# RELAY12.net
KiCad netlist of a schematic drawn in Altium Designer
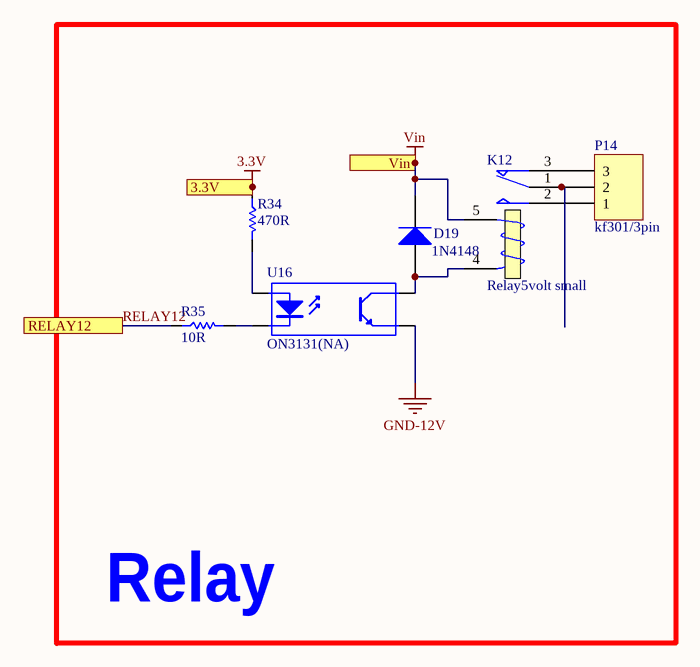
[diagram p0: RELAY12.SchDoc]

(export (version "E")
  (design (tool "Eeschema 10.0.6"))
  (components
    (comp (ref "D19")
      (value "1N4148")
      (footprint "sod123")
      (description "1 Amp General Purpose Rectifier")
      (fields (field (name "PUBLISHER") "Altium Limited"))
      (libsource (lib "Miscellaneous Devices") (part "Diode 1N4007"))
    )
    (comp (ref "K12")
      (value "Relay5volt small")
      (footprint "relay5_childern")
      (description "SPDT Relay")
      (fields (field (name "PUBLISHER") "Altium Limited"))
      (libsource (lib "FLIB") (part "Relay"))
    )
    (comp (ref "P14")
      (value "kf301/3pin")
      (footprint "Blue Connector 1*3 -kf301")
      (fields (field (name "PUBLISHER") "Altium Limited"))
      (libsource (lib "Miscellaneous Connectors") (part "Header 3"))
    )
    (comp (ref "R34")
      (value "470R")
      (footprint "0805/resistor")
      (description "Resistor")
      (fields (field (name "TOLERANCE") "5%") (field (name "POWER") "1/8 W"))
      (libsource (lib "skille") (part "Resistor"))
    )
    (comp (ref "R35")
      (value "10R")
      (footprint "0805/resistor")
      (description "Resistor")
      (fields (field (name "TOLERANCE") "5%") (field (name "POWER") "1/8 W"))
      (libsource (lib "skille") (part "Resistor"))
    )
    (comp (ref "U16")
      (value "ON3131(NA)")
      (footprint "OPTO_COUPLER")
      (description "4-Pin Phototransistor Optocoupler")
      (fields (field (name "PUBLISHER") "Altium Limited"))
      (libsource (lib "skille") (part "Optoisolator1"))
    )
  )
  (nets
    (net (code "1") (name "/RELAY12") (class "Default")
      (node (ref "R35") (pin "1") (pinfunction "1_1") (pintype "passive"))
    )
    (net (code "2") (name "3.3V") (class "Default")
      (node (ref "R34") (pin "1") (pinfunction "1_1") (pintype "passive"))
    )
    (net (code "3") (name "GND-12V") (class "Default")
      (node (ref "U16") (pin "3") (pinfunction "E_3") (pintype "passive"))
    )
    (net (code "4") (name "Net-(K12-COM)") (class "Default")
      (node (ref "K12") (pin "1") (pinfunction "COM_1") (pintype "passive"))
      (node (ref "P14") (pin "2") (pinfunction "2_2") (pintype "passive"))
    )
    (net (code "5") (name "Net-(K12-NO)") (class "Default")
      (node (ref "K12") (pin "2") (pinfunction "NO_2") (pintype "passive"))
      (node (ref "P14") (pin "1") (pinfunction "1_1") (pintype "passive"))
    )
    (net (code "6") (name "Net-(K12-T1)") (class "Default")
      (node (ref "K12") (pin "3") (pinfunction "T1_3") (pintype "passive"))
      (node (ref "P14") (pin "3") (pinfunction "3_3") (pintype "passive"))
    )
    (net (code "7") (name "Net-(K12-T2)") (class "Default")
      (node (ref "D19") (pin "A") (pinfunction "A_A") (pintype "passive"))
      (node (ref "K12") (pin "4") (pinfunction "T2_4") (pintype "passive"))
      (node (ref "U16") (pin "4") (pinfunction "C_4") (pintype "passive"))
    )
    (net (code "8") (name "Net-(U16-A)") (class "Default")
      (node (ref "R34") (pin "2") (pinfunction "2_2") (pintype "passive"))
      (node (ref "U16") (pin "1") (pinfunction "A_1") (pintype "passive"))
    )
    (net (code "9") (name "Net-(U16-K)") (class "Default")
      (node (ref "R35") (pin "2") (pinfunction "2_2") (pintype "passive"))
      (node (ref "U16") (pin "2") (pinfunction "K_2") (pintype "passive"))
    )
    (net (code "10") (name "Vin") (class "Default")
      (node (ref "D19") (pin "K") (pinfunction "K_K") (pintype "passive"))
      (node (ref "K12") (pin "5") (pinfunction "5_5") (pintype "passive"))
    )
  )
)
